# GPRS_A7.net
KiCad netlist of a schematic drawn in EAGLE
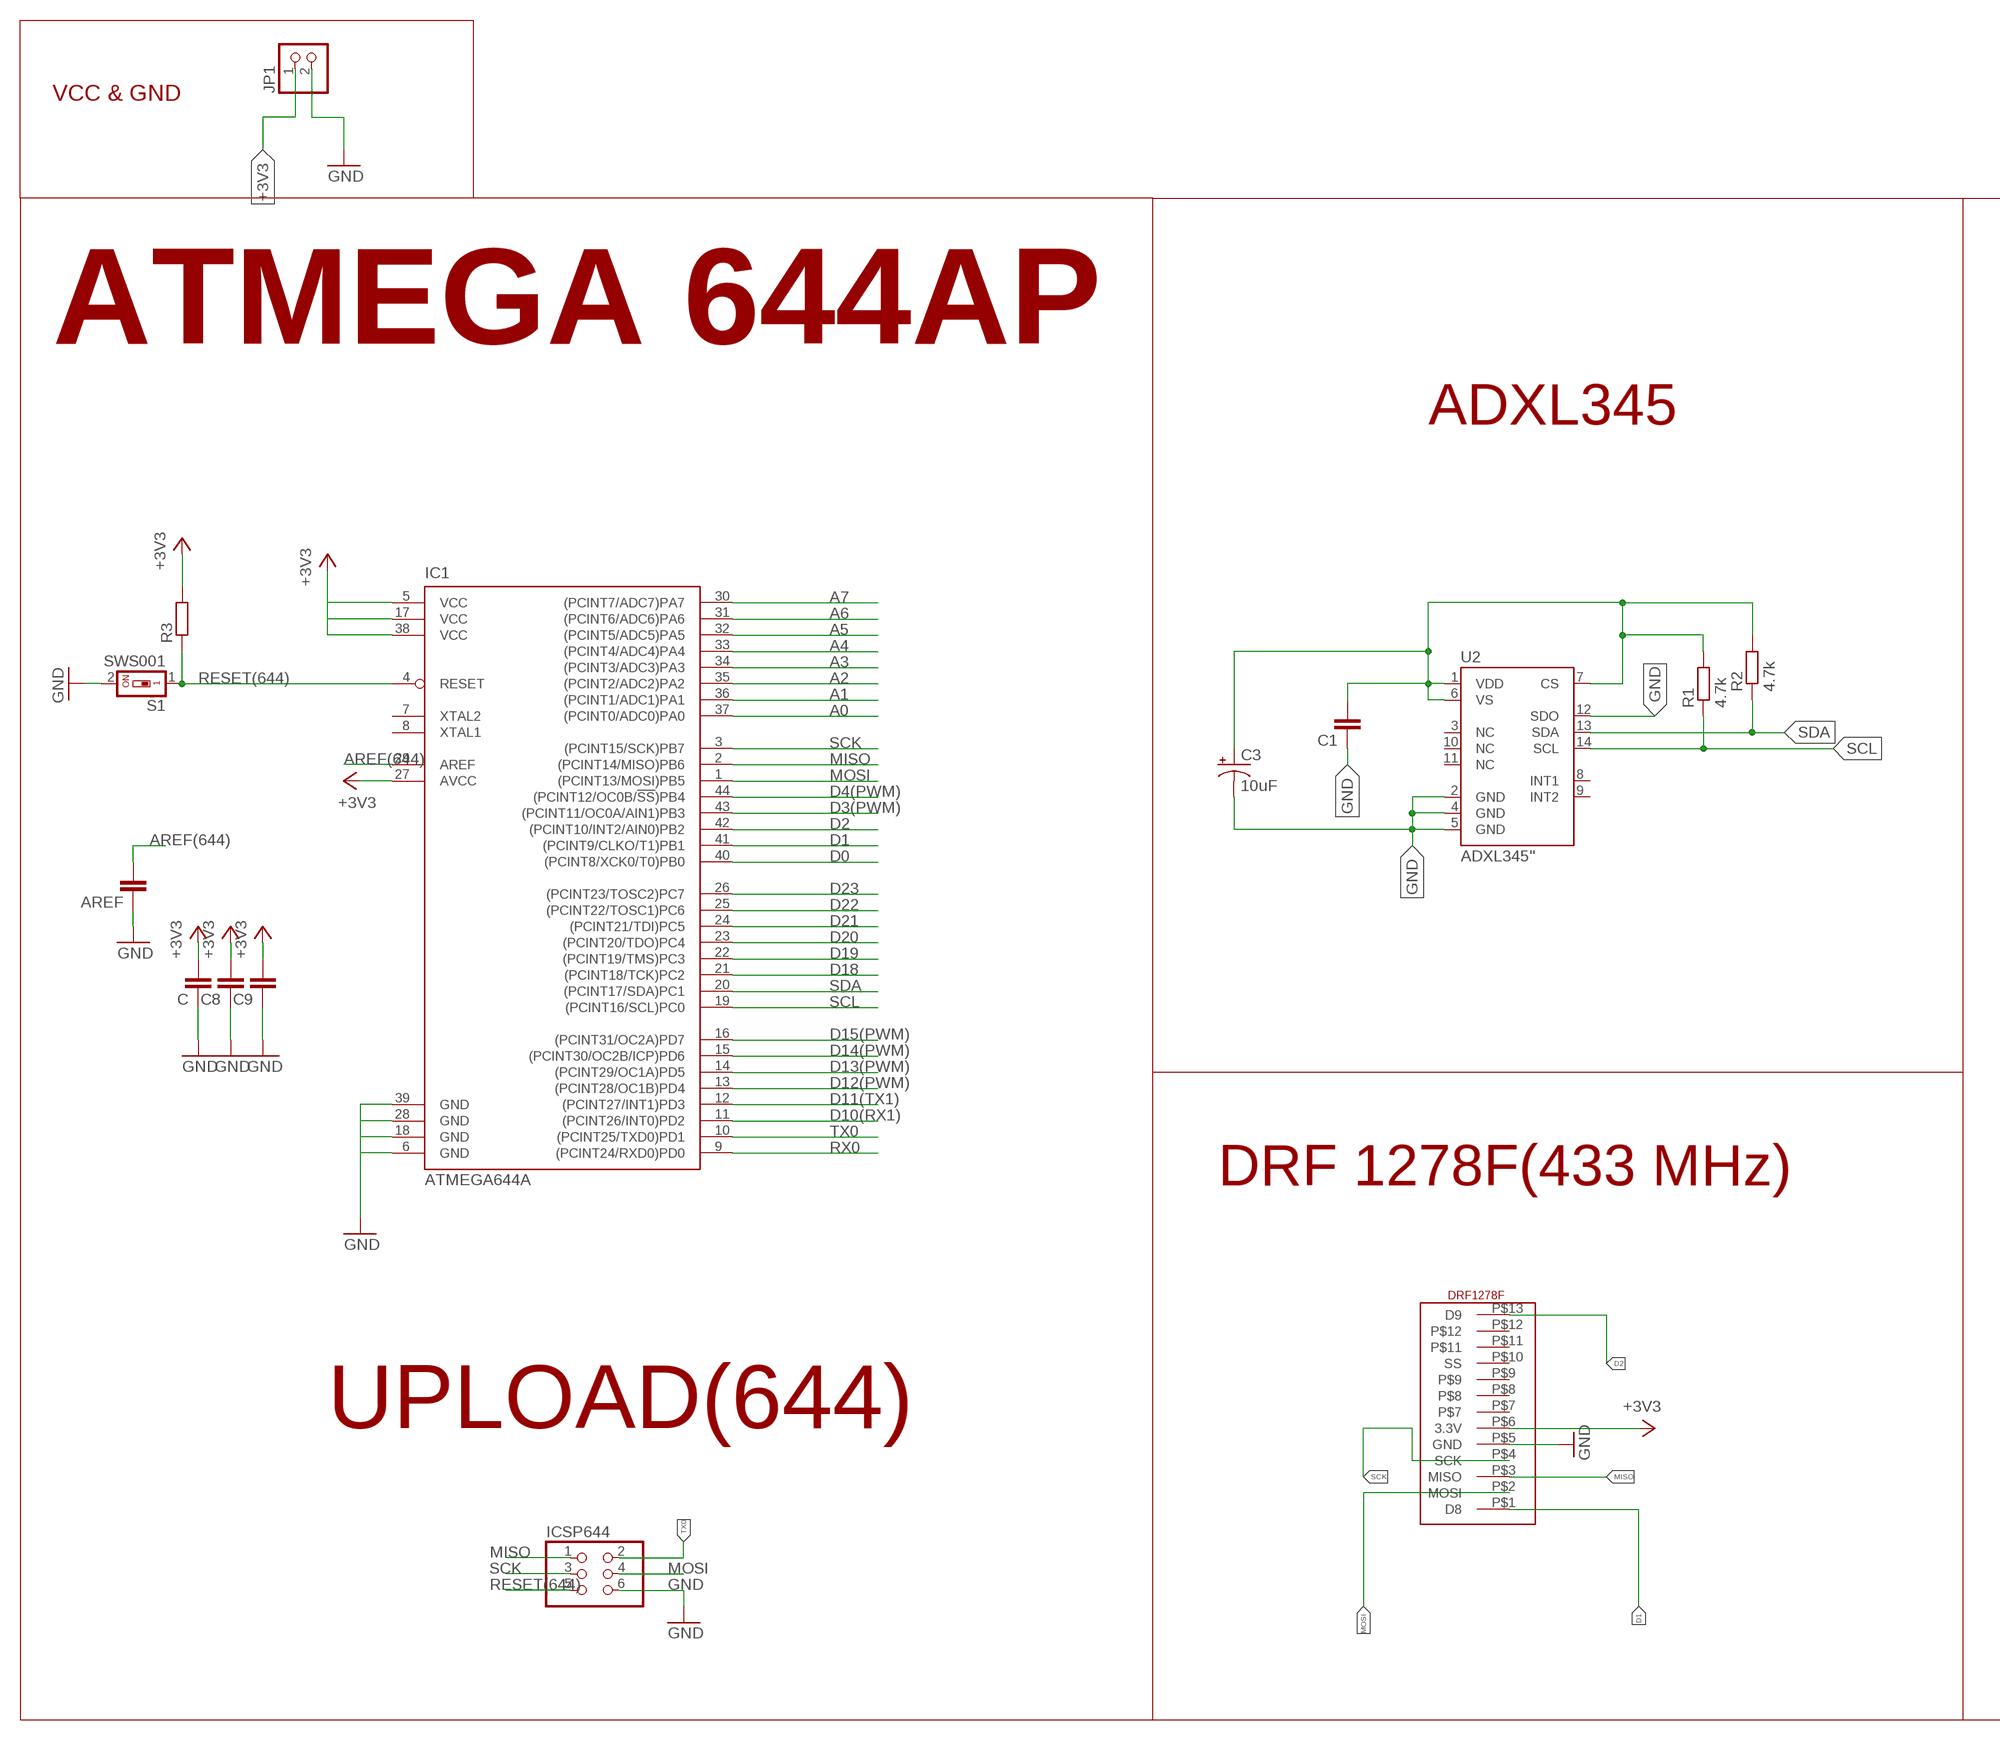
[diagram p0: schematic, sheet 1, part 1 of 2]
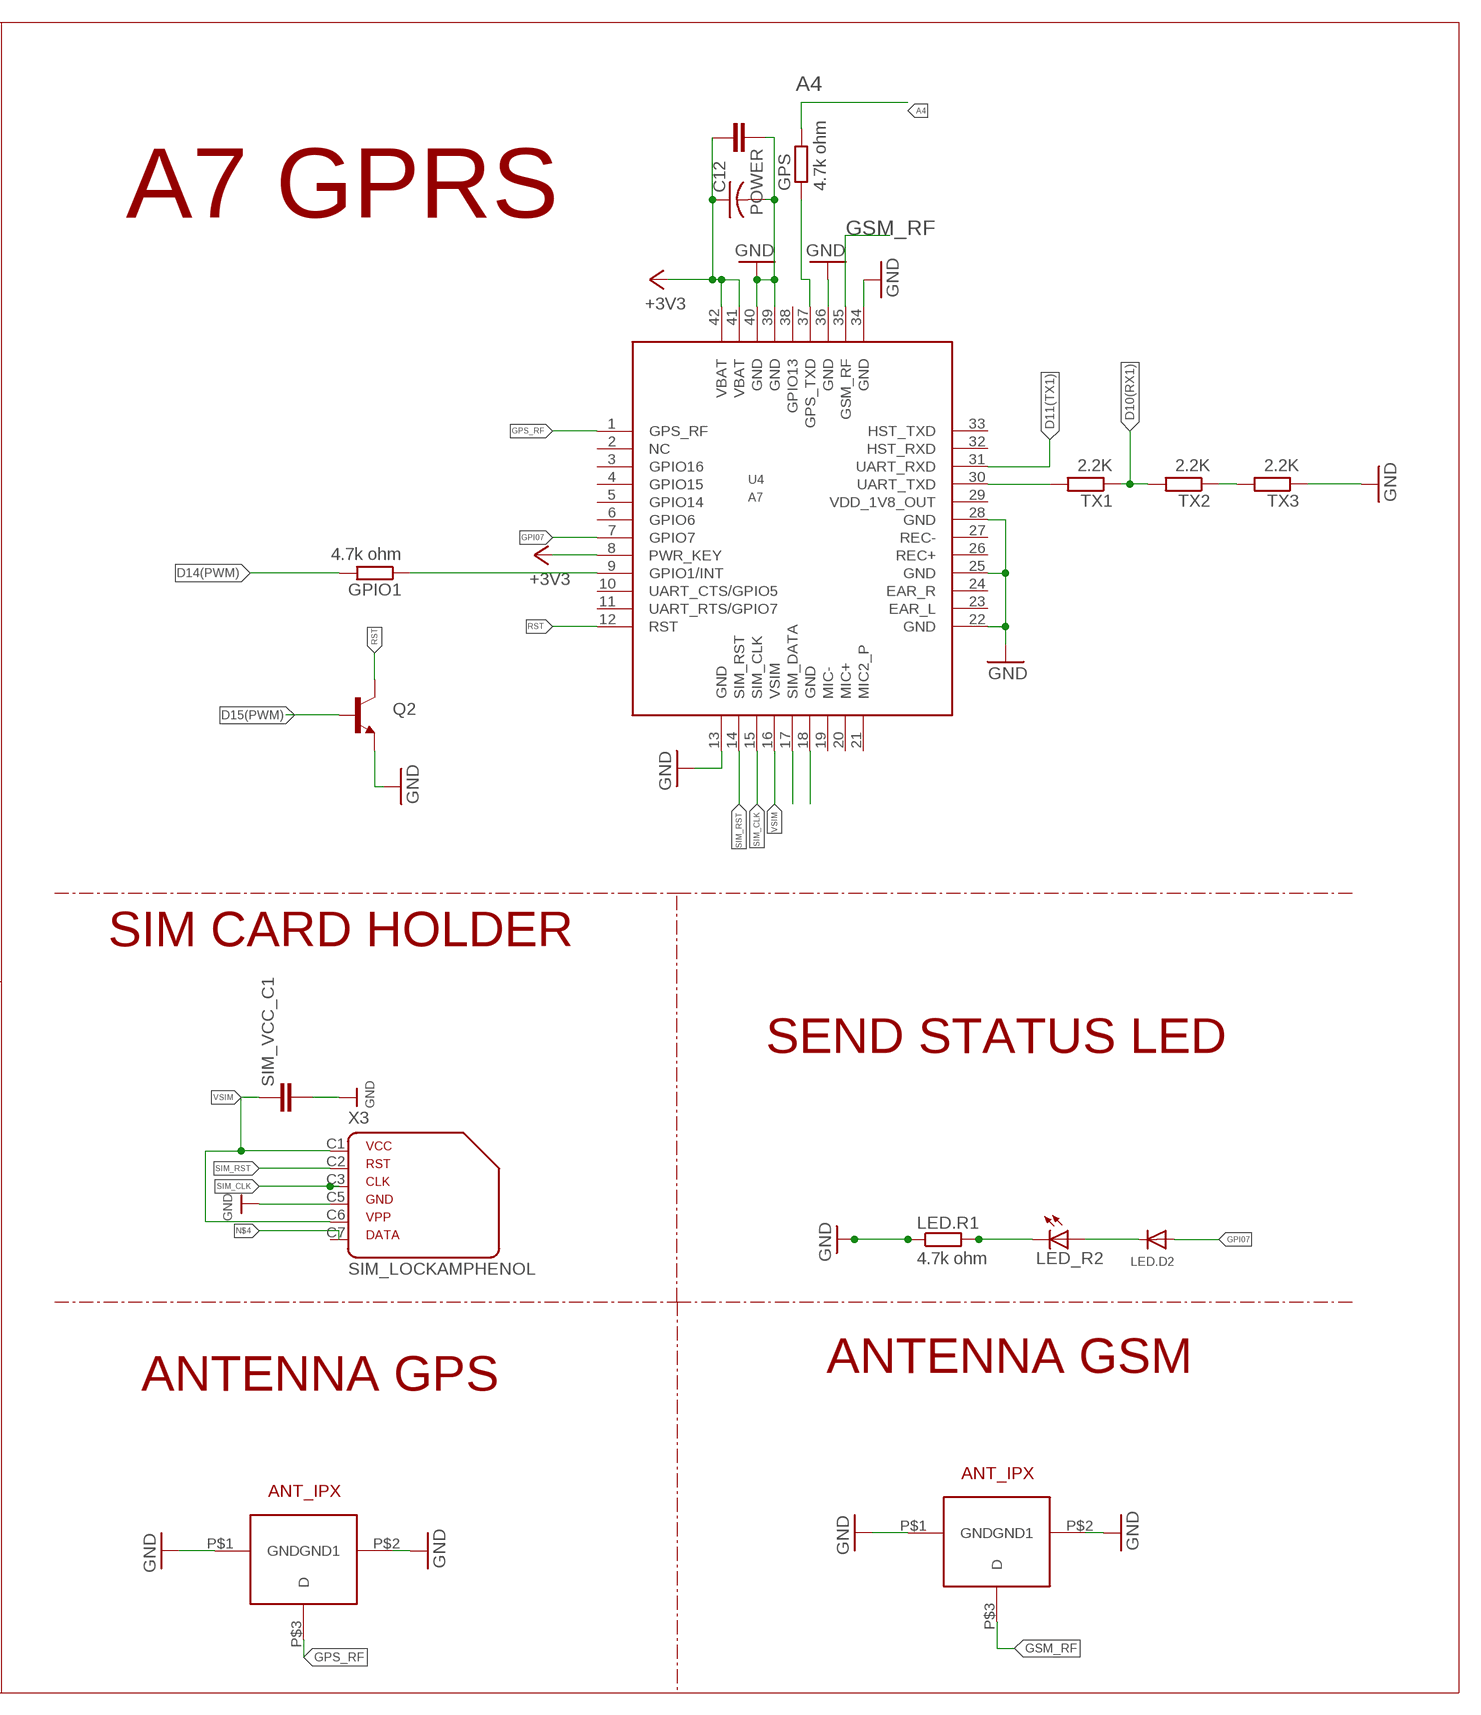
[diagram p1: schematic, sheet 1, part 2 of 2]

(export (version "E")
  (design (tool "Eeschema 10.0.6"))
  (components
    (comp (ref "AREF")
      (value "100nF")
      (footprint "eagle-import:C0805")
      (libsource (lib "eagle-import") (part "C-EUC0805"))
    )
    (comp (ref "C")
      (value "22 uF")
      (footprint "eagle-import:C0805")
      (libsource (lib "eagle-import") (part "C-EUC0805"))
    )
    (comp (ref "C1")
      (value "0.1uF")
      (footprint "eagle-import:C0805")
      (libsource (lib "eagle-import") (part "C-EUC0805"))
    )
    (comp (ref "C3")
      (value "10uF")
      (footprint "eagle-import:EIA3216")
      (libsource (lib "eagle-import") (part "CAP_POL1206"))
    )
    (comp (ref "C8")
      (value "100nF")
      (footprint "eagle-import:C0805")
      (libsource (lib "eagle-import") (part "C-EUC0805"))
    )
    (comp (ref "C9")
      (value "100nF")
      (footprint "eagle-import:C0805")
      (libsource (lib "eagle-import") (part "C-EUC0805"))
    )
    (comp (ref "C12")
      (value "C-US025-024X044")
      (footprint "eagle-import:C025-024X044")
      (libsource (lib "eagle-import") (part "C-US025-024X044"))
    )
    (comp (ref "GPIO1")
      (value "4.7k ohm")
      (footprint "eagle-import:R0805")
      (libsource (lib "eagle-import") (part "R-EU_R0805"))
    )
    (comp (ref "GPS")
      (value "4.7k ohm")
      (footprint "eagle-import:R0805")
      (libsource (lib "eagle-import") (part "R-EU_R0805"))
    )
    (comp (ref "IC1")
      (value "ATMEGA644A")
      (footprint "eagle-import:TQFP44")
      (fields (field (name "MPN") "ATMEGA644PV-10AU"))
      (libsource (lib "eagle-import") (part "ATMEGA644A"))
    )
    (comp (ref "ICSP644")
      (value "PINHD-2X3")
      (footprint "eagle-import:2X03")
      (libsource (lib "eagle-import") (part "PINHD-2X3"))
    )
    (comp (ref "JP1")
      (value "PINHD-1X2")
      (footprint "eagle-import:1X02")
      (libsource (lib "eagle-import") (part "PINHD-1X2"))
    )
    (comp (ref "LED.D2")
      (value "DIODESOD-123")
      (footprint "eagle-import:SOD-123")
      (libsource (lib "eagle-import") (part "DIODESOD-123"))
    )
    (comp (ref "LED.R1")
      (value "4.7k ohm")
      (footprint "eagle-import:R0805")
      (libsource (lib "eagle-import") (part "R-EU_R0805"))
    )
    (comp (ref "LED_R2")
      (value "LEDCHIP-LED0805")
      (footprint "eagle-import:CHIP-LED0805")
      (libsource (lib "eagle-import") (part "LEDCHIP-LED0805"))
    )
    (comp (ref "POWER")
      (value "100nF")
      (footprint "eagle-import:C0805")
      (libsource (lib "eagle-import") (part "C-EUC0805"))
    )
    (comp (ref "Q2")
      (value "TRANSISTOR_NPNSOT23-3")
      (footprint "eagle-import:SOT23-3")
      (libsource (lib "eagle-import") (part "TRANSISTOR_NPNSOT23-3"))
    )
    (comp (ref "R1")
      (value "4.7k")
      (footprint "eagle-import:R0805")
      (libsource (lib "eagle-import") (part "R-EU_R0805"))
    )
    (comp (ref "R2")
      (value "4.7k")
      (footprint "eagle-import:R0805")
      (libsource (lib "eagle-import") (part "R-EU_R0805"))
    )
    (comp (ref "R3")
      (value "R-EU_R0805")
      (footprint "eagle-import:R0805")
      (libsource (lib "eagle-import") (part "R-EU_R0805"))
    )
    (comp (ref "S1")
      (value "SWS001")
      (footprint "eagle-import:SMS-001")
      (libsource (lib "eagle-import") (part "SWS001"))
    )
    (comp (ref "SIM_VCC_C1")
      (value "100nF")
      (footprint "eagle-import:C0805")
      (libsource (lib "eagle-import") (part "C-EUC0805"))
    )
    (comp (ref "TX1")
      (value "2.2K")
      (footprint "eagle-import:R0805")
      (libsource (lib "eagle-import") (part "R-EU_R0805"))
    )
    (comp (ref "TX2")
      (value "2.2K")
      (footprint "eagle-import:R0805")
      (libsource (lib "eagle-import") (part "R-EU_R0805"))
    )
    (comp (ref "TX3")
      (value "2.2K")
      (footprint "eagle-import:R0805")
      (libsource (lib "eagle-import") (part "R-EU_R0805"))
    )
    (comp (ref "U$1")
      (value "DRF1278F")
      (footprint "eagle-import:DIP13")
      (libsource (lib "eagle-import") (part "DRF1278F"))
    )
    (comp (ref "U$2")
      (value "ANTENNA_IPX")
      (footprint "eagle-import:SMD3")
      (libsource (lib "eagle-import") (part "ANTENNA_IPX"))
    )
    (comp (ref "U$9")
      (value "ANTENNA_IPX")
      (footprint "eagle-import:SMD3")
      (libsource (lib "eagle-import") (part "ANTENNA_IPX"))
    )
    (comp (ref "U2")
      (value "ADXL345\"")
      (footprint "eagle-import:ADXL3451_1")
      (libsource (lib "eagle-import") (part "ADXL345{dblquote}"))
    )
    (comp (ref "U4") (value "A7") (footprint "eagle-import:A7") (libsource (lib "eagle-import") (part "A7")))
    (comp (ref "X3")
      (value "SIM_LOCKAMPHENOL")
      (footprint "eagle-import:C707_10M006_512_2")
      (libsource (lib "eagle-import") (part "SIM_LOCKAMPHENOL"))
    )
  )
  (nets
    (net (code "1") (name "+3V3") (class "Default")
      (node (ref "C") (pin "2") (pinfunction "2_2") (pintype "passive"))
      (node (ref "C12") (pin "1") (pinfunction "1_1") (pintype "passive"))
      (node (ref "C8") (pin "2") (pinfunction "2_2") (pintype "passive"))
      (node (ref "C9") (pin "2") (pinfunction "2_2") (pintype "passive"))
      (node (ref "IC1") (pin "17") (pinfunction "VCC_17") (pintype "power_in"))
      (node (ref "IC1") (pin "27") (pinfunction "AVCC_27") (pintype "power_in"))
      (node (ref "IC1") (pin "38") (pinfunction "VCC_38") (pintype "power_in"))
      (node (ref "IC1") (pin "5") (pinfunction "VCC_5") (pintype "power_in"))
      (node (ref "JP1") (pin "1") (pinfunction "1_1") (pintype "passive"))
      (node (ref "POWER") (pin "2") (pinfunction "2_2") (pintype "passive"))
      (node (ref "R3") (pin "2") (pinfunction "2_2") (pintype "passive"))
      (node (ref "U$1") (pin "P$6") (pinfunction "3.3V_P$6") (pintype "bidirectional"))
      (node (ref "U4") (pin "41") (pinfunction "VBAT_41") (pintype "bidirectional"))
      (node (ref "U4") (pin "42") (pinfunction "VBAT_42") (pintype "bidirectional"))
      (node (ref "U4") (pin "8") (pinfunction "PWR_KEY_8") (pintype "bidirectional"))
    )
    (net (code "2") (name "/A0") (class "Default")
      (node (ref "IC1") (pin "37") (pinfunction "(PCINT0/ADC0)PA0_37") (pintype "bidirectional"))
    )
    (net (code "3") (name "/A1") (class "Default")
      (node (ref "IC1") (pin "36") (pinfunction "(PCINT1/ADC1)PA1_36") (pintype "bidirectional"))
    )
    (net (code "4") (name "/A2") (class "Default")
      (node (ref "IC1") (pin "35") (pinfunction "(PCINT2/ADC2)PA2_35") (pintype "bidirectional"))
    )
    (net (code "5") (name "/A3") (class "Default")
      (node (ref "IC1") (pin "34") (pinfunction "(PCINT3/ADC3)PA3_34") (pintype "bidirectional"))
    )
    (net (code "6") (name "/A5") (class "Default")
      (node (ref "IC1") (pin "32") (pinfunction "(PCINT5/ADC5)PA5_32") (pintype "bidirectional"))
    )
    (net (code "7") (name "/A6") (class "Default")
      (node (ref "IC1") (pin "31") (pinfunction "(PCINT6/ADC6)PA6_31") (pintype "bidirectional"))
    )
    (net (code "8") (name "/A7") (class "Default")
      (node (ref "IC1") (pin "30") (pinfunction "(PCINT7/ADC7)PA7_30") (pintype "bidirectional"))
    )
    (net (code "9") (name "/AREF(644)") (class "Default")
      (node (ref "AREF") (pin "2") (pinfunction "2_2") (pintype "passive"))
      (node (ref "IC1") (pin "29") (pinfunction "AREF_29") (pintype "passive"))
    )
    (net (code "10") (name "/D0") (class "Default")
      (node (ref "IC1") (pin "40") (pinfunction "(PCINT8/XCK0/T0)PB0_40") (pintype "bidirectional"))
    )
    (net (code "11") (name "/D3(PWM)") (class "Default")
      (node (ref "IC1") (pin "43") (pinfunction "(PCINT11/OC0A/AIN1)PB3_43") (pintype "bidirectional"))
    )
    (net (code "12") (name "/D4(PWM)") (class "Default")
      (node (ref "IC1") (pin "44") (pinfunction "(PCINT12/OC0B/~{SS})PB4_44") (pintype "bidirectional"))
    )
    (net (code "13") (name "/D12(PWM)") (class "Default")
      (node (ref "IC1") (pin "13") (pinfunction "(PCINT28/OC1B)PD4_13") (pintype "bidirectional"))
    )
    (net (code "14") (name "/D13(PWM)") (class "Default")
      (node (ref "IC1") (pin "14") (pinfunction "(PCINT29/OC1A)PD5_14") (pintype "bidirectional"))
    )
    (net (code "15") (name "/D18") (class "Default")
      (node (ref "IC1") (pin "21") (pinfunction "(PCINT18/TCK)PC2_21") (pintype "output"))
    )
    (net (code "16") (name "/D19") (class "Default")
      (node (ref "IC1") (pin "22") (pinfunction "(PCINT19/TMS)PC3_22") (pintype "output"))
    )
    (net (code "17") (name "/D20") (class "Default")
      (node (ref "IC1") (pin "23") (pinfunction "(PCINT20/TDO)PC4_23") (pintype "output"))
    )
    (net (code "18") (name "/D21") (class "Default")
      (node (ref "IC1") (pin "24") (pinfunction "(PCINT21/TDI)PC5_24") (pintype "output"))
    )
    (net (code "19") (name "/D22") (class "Default")
      (node (ref "IC1") (pin "25") (pinfunction "(PCINT22/TOSC1)PC6_25") (pintype "output"))
    )
    (net (code "20") (name "/D23") (class "Default")
      (node (ref "IC1") (pin "26") (pinfunction "(PCINT23/TOSC2)PC7_26") (pintype "output"))
    )
    (net (code "21") (name "/RESET(644)") (class "Default")
      (node (ref "IC1") (pin "4") (pinfunction "RESET_4") (pintype "input"))
      (node (ref "ICSP644") (pin "5") (pinfunction "5_5") (pintype "passive"))
      (node (ref "R3") (pin "1") (pinfunction "1_1") (pintype "passive"))
      (node (ref "S1") (pin "1") (pinfunction "1_1") (pintype "passive"))
    )
    (net (code "22") (name "/RX0") (class "Default")
      (node (ref "IC1") (pin "9") (pinfunction "(PCINT24/RXD0)PD0_9") (pintype "bidirectional"))
    )
    (net (code "23") (name "A4") (class "Default")
      (node (ref "GPS") (pin "2") (pinfunction "2_2") (pintype "passive"))
      (node (ref "IC1") (pin "33") (pinfunction "(PCINT4/ADC4)PA4_33") (pintype "bidirectional"))
    )
    (net (code "24") (name "D1") (class "Default")
      (node (ref "IC1") (pin "41") (pinfunction "(PCINT9/CLKO/T1)PB1_41") (pintype "bidirectional"))
      (node (ref "U$1") (pin "P$1") (pinfunction "D8_P$1") (pintype "bidirectional"))
    )
    (net (code "25") (name "D2") (class "Default")
      (node (ref "IC1") (pin "42") (pinfunction "(PCINT10/INT2/AIN0)PB2_42") (pintype "bidirectional"))
      (node (ref "U$1") (pin "P$13") (pinfunction "D9_P$13") (pintype "bidirectional"))
    )
    (net (code "26") (name "D10(RX1)") (class "Default")
      (node (ref "IC1") (pin "11") (pinfunction "(PCINT26/INT0)PD2_11") (pintype "bidirectional"))
      (node (ref "TX1") (pin "1") (pinfunction "1_1") (pintype "passive"))
      (node (ref "TX2") (pin "2") (pinfunction "2_2") (pintype "passive"))
    )
    (net (code "27") (name "D11(TX1)") (class "Default")
      (node (ref "IC1") (pin "12") (pinfunction "(PCINT27/INT1)PD3_12") (pintype "bidirectional"))
      (node (ref "U4") (pin "31") (pinfunction "UART_RXD_31") (pintype "bidirectional"))
    )
    (net (code "28") (name "D14(PWM)") (class "Default")
      (node (ref "GPIO1") (pin "2") (pinfunction "2_2") (pintype "passive"))
      (node (ref "IC1") (pin "15") (pinfunction "(PCINT30/OC2B/ICP)PD6_15") (pintype "bidirectional"))
    )
    (net (code "29") (name "D15(PWM)") (class "Default")
      (node (ref "IC1") (pin "16") (pinfunction "(PCINT31/OC2A)PD7_16") (pintype "bidirectional"))
      (node (ref "Q2") (pin "1") (pinfunction "B_1") (pintype "passive"))
    )
    (net (code "30") (name "GND") (class "Default")
      (node (ref "AREF") (pin "1") (pinfunction "1_1") (pintype "passive"))
      (node (ref "C") (pin "1") (pinfunction "1_1") (pintype "passive"))
      (node (ref "C1") (pin "1") (pinfunction "1_1") (pintype "passive"))
      (node (ref "C12") (pin "2") (pinfunction "2_2") (pintype "passive"))
      (node (ref "C3") (pin "C") (pinfunction "-_C") (pintype "passive"))
      (node (ref "C8") (pin "1") (pinfunction "1_1") (pintype "passive"))
      (node (ref "C9") (pin "1") (pinfunction "1_1") (pintype "passive"))
      (node (ref "IC1") (pin "18") (pinfunction "GND_18") (pintype "power_in"))
      (node (ref "IC1") (pin "28") (pinfunction "GND_28") (pintype "power_in"))
      (node (ref "IC1") (pin "39") (pinfunction "GND_39") (pintype "power_in"))
      (node (ref "IC1") (pin "6") (pinfunction "GND_6") (pintype "power_in"))
      (node (ref "ICSP644") (pin "6") (pinfunction "6_6") (pintype "passive"))
      (node (ref "JP1") (pin "2") (pinfunction "2_2") (pintype "passive"))
      (node (ref "LED.R1") (pin "1") (pinfunction "1_1") (pintype "passive"))
      (node (ref "POWER") (pin "1") (pinfunction "1_1") (pintype "passive"))
      (node (ref "Q2") (pin "2") (pinfunction "E_2") (pintype "passive"))
      (node (ref "S1") (pin "2") (pinfunction "2_2") (pintype "passive"))
      (node (ref "SIM_VCC_C1") (pin "2") (pinfunction "2_2") (pintype "passive"))
      (node (ref "TX3") (pin "1") (pinfunction "1_1") (pintype "passive"))
      (node (ref "U$1") (pin "P$5") (pinfunction "GND_P$5") (pintype "bidirectional"))
      (node (ref "U$2") (pin "P$1") (pinfunction "GND_P$1") (pintype "bidirectional"))
      (node (ref "U$2") (pin "P$2") (pinfunction "GND1_P$2") (pintype "bidirectional"))
      (node (ref "U$9") (pin "P$1") (pinfunction "GND_P$1") (pintype "bidirectional"))
      (node (ref "U$9") (pin "P$2") (pinfunction "GND1_P$2") (pintype "bidirectional"))
      (node (ref "U2") (pin "12") (pinfunction "SDO_12") (pintype "bidirectional"))
      (node (ref "U2") (pin "2") (pinfunction "GND_2") (pintype "bidirectional"))
      (node (ref "U2") (pin "4") (pinfunction "GND_4") (pintype "bidirectional"))
      (node (ref "U2") (pin "5") (pinfunction "GND_5") (pintype "bidirectional"))
      (node (ref "U4") (pin "13") (pinfunction "GND_13") (pintype "bidirectional"))
      (node (ref "U4") (pin "22") (pinfunction "GND_22") (pintype "bidirectional"))
      (node (ref "U4") (pin "25") (pinfunction "GND_25") (pintype "bidirectional"))
      (node (ref "U4") (pin "28") (pinfunction "GND_28") (pintype "bidirectional"))
      (node (ref "U4") (pin "34") (pinfunction "GND_34") (pintype "bidirectional"))
      (node (ref "U4") (pin "36") (pinfunction "GND_36") (pintype "bidirectional"))
      (node (ref "U4") (pin "39") (pinfunction "GND_39") (pintype "bidirectional"))
      (node (ref "U4") (pin "40") (pinfunction "GND_40") (pintype "bidirectional"))
      (node (ref "X3") (pin "C5") (pinfunction "4_C5") (pintype "passive"))
    )
    (net (code "31") (name "GPI07") (class "Default")
      (node (ref "LED.D2") (pin "A") (pinfunction "A_A") (pintype "passive"))
      (node (ref "U4") (pin "7") (pinfunction "GPIO7_7") (pintype "bidirectional"))
    )
    (net (code "32") (name "GPS_RF") (class "Default")
      (node (ref "U$2") (pin "P$3") (pinfunction "D_P$3") (pintype "bidirectional"))
      (node (ref "U4") (pin "1") (pinfunction "GPS_RF_1") (pintype "bidirectional"))
    )
    (net (code "33") (name "GSM_RF") (class "Default")
      (node (ref "U$9") (pin "P$3") (pinfunction "D_P$3") (pintype "bidirectional"))
      (node (ref "U4") (pin "35") (pinfunction "GSM_RF_35") (pintype "bidirectional"))
    )
    (net (code "34") (name "MISO") (class "Default")
      (node (ref "IC1") (pin "2") (pinfunction "(PCINT14/MISO)PB6_2") (pintype "bidirectional"))
      (node (ref "ICSP644") (pin "1") (pinfunction "1_1") (pintype "passive"))
      (node (ref "U$1") (pin "P$3") (pinfunction "MISO_P$3") (pintype "bidirectional"))
    )
    (net (code "35") (name "MOSI") (class "Default")
      (node (ref "IC1") (pin "1") (pinfunction "(PCINT13/MOSI)PB5_1") (pintype "bidirectional"))
      (node (ref "ICSP644") (pin "4") (pinfunction "4_4") (pintype "passive"))
      (node (ref "U$1") (pin "P$2") (pinfunction "MOSI_P$2") (pintype "bidirectional"))
    )
    (net (code "37") (name "Net-(C3-+)") (class "Default")
      (node (ref "C1") (pin "2") (pinfunction "2_2") (pintype "passive"))
      (node (ref "C3") (pin "A") (pinfunction "+_A") (pintype "passive"))
      (node (ref "R1") (pin "2") (pinfunction "2_2") (pintype "passive"))
      (node (ref "R2") (pin "2") (pinfunction "2_2") (pintype "passive"))
      (node (ref "U2") (pin "1") (pinfunction "VDD_1") (pintype "bidirectional"))
      (node (ref "U2") (pin "6") (pinfunction "VS_6") (pintype "bidirectional"))
      (node (ref "U2") (pin "7") (pinfunction "CS_7") (pintype "bidirectional"))
    )
    (net (code "38") (name "Net-(LED.D2-PadC)") (class "Default")
      (node (ref "LED.D2") (pin "C") (pinfunction "C_C") (pintype "passive"))
      (node (ref "LED_R2") (pin "A") (pinfunction "A_A") (pintype "passive"))
    )
    (net (code "39") (name "Net-(LED.R1-Pad2)") (class "Default")
      (node (ref "LED.R1") (pin "2") (pinfunction "2_2") (pintype "passive"))
      (node (ref "LED_R2") (pin "C") (pinfunction "C_C") (pintype "passive"))
    )
    (net (code "40") (name "Net-(TX2-Pad1)") (class "Default")
      (node (ref "TX2") (pin "1") (pinfunction "1_1") (pintype "passive"))
      (node (ref "TX3") (pin "2") (pinfunction "2_2") (pintype "passive"))
    )
    (net (code "41") (name "Net-(U4-GPIO1{slash}INT)") (class "Default")
      (node (ref "GPIO1") (pin "1") (pinfunction "1_1") (pintype "passive"))
      (node (ref "U4") (pin "9") (pinfunction "GPIO1/INT_9") (pintype "bidirectional"))
    )
    (net (code "42") (name "Net-(U4-GPS_TXD)") (class "Default")
      (node (ref "GPS") (pin "1") (pinfunction "1_1") (pintype "passive"))
      (node (ref "U4") (pin "37") (pinfunction "GPS_TXD_37") (pintype "bidirectional"))
    )
    (net (code "43") (name "Net-(U4-UART_TXD)") (class "Default")
      (node (ref "TX1") (pin "2") (pinfunction "2_2") (pintype "passive"))
      (node (ref "U4") (pin "30") (pinfunction "UART_TXD_30") (pintype "bidirectional"))
    )
    (net (code "44") (name "RST") (class "Default")
      (node (ref "Q2") (pin "3") (pinfunction "C_3") (pintype "passive"))
      (node (ref "U4") (pin "12") (pinfunction "RST_12") (pintype "bidirectional"))
    )
    (net (code "45") (name "SCK") (class "Default")
      (node (ref "IC1") (pin "3") (pinfunction "(PCINT15/SCK)PB7_3") (pintype "bidirectional"))
      (node (ref "ICSP644") (pin "3") (pinfunction "3_3") (pintype "passive"))
      (node (ref "U$1") (pin "P$4") (pinfunction "SCK_P$4") (pintype "bidirectional"))
    )
    (net (code "46") (name "SCL") (class "Default")
      (node (ref "IC1") (pin "19") (pinfunction "(PCINT16/SCL)PC0_19") (pintype "output"))
      (node (ref "R1") (pin "1") (pinfunction "1_1") (pintype "passive"))
      (node (ref "U2") (pin "14") (pinfunction "SCL_14") (pintype "bidirectional"))
    )
    (net (code "47") (name "SDA") (class "Default")
      (node (ref "IC1") (pin "20") (pinfunction "(PCINT17/SDA)PC1_20") (pintype "output"))
      (node (ref "R2") (pin "1") (pinfunction "1_1") (pintype "passive"))
      (node (ref "U2") (pin "13") (pinfunction "SDA_13") (pintype "bidirectional"))
    )
    (net (code "48") (name "SIM_CLK") (class "Default")
      (node (ref "U4") (pin "15") (pinfunction "SIM_CLK_15") (pintype "bidirectional"))
      (node (ref "X3") (pin "C3") (pinfunction "3_C3") (pintype "passive"))
    )
    (net (code "49") (name "SIM_RST") (class "Default")
      (node (ref "U4") (pin "14") (pinfunction "SIM_RST_14") (pintype "bidirectional"))
      (node (ref "X3") (pin "C2") (pinfunction "2_C2") (pintype "passive"))
    )
    (net (code "50") (name "TX0") (class "Default")
      (node (ref "IC1") (pin "10") (pinfunction "(PCINT25/TXD0)PD1_10") (pintype "bidirectional"))
      (node (ref "ICSP644") (pin "2") (pinfunction "2_2") (pintype "passive"))
    )
    (net (code "51") (name "VSIM") (class "Default")
      (node (ref "SIM_VCC_C1") (pin "1") (pinfunction "1_1") (pintype "passive"))
      (node (ref "U4") (pin "16") (pinfunction "VSIM_16") (pintype "bidirectional"))
      (node (ref "X3") (pin "C1") (pinfunction "1_C1") (pintype "passive"))
      (node (ref "X3") (pin "C6") (pinfunction "5_C6") (pintype "passive"))
    )
    (net (code "52") (name "unconnected-(IC1-XTAL1-Pad8)") (class "Default")
      (node (ref "IC1") (pin "8") (pinfunction "XTAL1_8") (pintype "bidirectional"))
    )
    (net (code "53") (name "unconnected-(IC1-XTAL2-Pad7)") (class "Default")
      (node (ref "IC1") (pin "7") (pinfunction "XTAL2_7") (pintype "bidirectional"))
    )
    (net (code "54") (name "unconnected-(U$1-PadP$7)") (class "Default")
      (node (ref "U$1") (pin "P$7") (pinfunction "P$7_P$7") (pintype "bidirectional"))
    )
    (net (code "55") (name "unconnected-(U$1-PadP$8)") (class "Default")
      (node (ref "U$1") (pin "P$8") (pinfunction "P$8_P$8") (pintype "bidirectional"))
    )
    (net (code "56") (name "unconnected-(U$1-PadP$9)") (class "Default")
      (node (ref "U$1") (pin "P$9") (pinfunction "P$9_P$9") (pintype "bidirectional"))
    )
    (net (code "57") (name "unconnected-(U$1-PadP$11)") (class "Default")
      (node (ref "U$1") (pin "P$11") (pinfunction "P$11_P$11") (pintype "bidirectional"))
    )
    (net (code "58") (name "unconnected-(U$1-PadP$12)") (class "Default")
      (node (ref "U$1") (pin "P$12") (pinfunction "P$12_P$12") (pintype "bidirectional"))
    )
    (net (code "59") (name "unconnected-(U$1-SS-PadP$10)") (class "Default")
      (node (ref "U$1") (pin "P$10") (pinfunction "SS_P$10") (pintype "bidirectional"))
    )
    (net (code "60") (name "unconnected-(U2-INT1-Pad8)") (class "Default")
      (node (ref "U2") (pin "8") (pinfunction "INT1_8") (pintype "bidirectional"))
    )
    (net (code "61") (name "unconnected-(U2-INT2-Pad9)") (class "Default")
      (node (ref "U2") (pin "9") (pinfunction "INT2_9") (pintype "bidirectional"))
    )
    (net (code "62") (name "unconnected-(U2-NC-Pad3)") (class "Default")
      (node (ref "U2") (pin "3") (pinfunction "NC_3") (pintype "bidirectional"))
    )
    (net (code "63") (name "unconnected-(U2-NC-Pad10)") (class "Default")
      (node (ref "U2") (pin "10") (pinfunction "NC_10") (pintype "bidirectional"))
    )
    (net (code "64") (name "unconnected-(U2-NC-Pad11)") (class "Default")
      (node (ref "U2") (pin "11") (pinfunction "NC_11") (pintype "bidirectional"))
    )
    (net (code "65") (name "unconnected-(U4-EAR_L-Pad23)") (class "Default")
      (node (ref "U4") (pin "23") (pinfunction "EAR_L_23") (pintype "bidirectional"))
    )
    (net (code "66") (name "unconnected-(U4-EAR_R-Pad24)") (class "Default")
      (node (ref "U4") (pin "24") (pinfunction "EAR_R_24") (pintype "bidirectional"))
    )
    (net (code "67") (name "unconnected-(U4-GND-Pad18)") (class "Default")
      (node (ref "U4") (pin "18") (pinfunction "GND_18") (pintype "bidirectional"))
    )
    (net (code "68") (name "unconnected-(U4-GPIO6-Pad6)") (class "Default")
      (node (ref "U4") (pin "6") (pinfunction "GPIO6_6") (pintype "bidirectional"))
    )
    (net (code "69") (name "unconnected-(U4-GPIO13-Pad38)") (class "Default")
      (node (ref "U4") (pin "38") (pinfunction "GPIO13_38") (pintype "bidirectional"))
    )
    (net (code "70") (name "unconnected-(U4-GPIO14-Pad5)") (class "Default")
      (node (ref "U4") (pin "5") (pinfunction "GPIO14_5") (pintype "bidirectional"))
    )
    (net (code "71") (name "unconnected-(U4-GPIO15-Pad4)") (class "Default")
      (node (ref "U4") (pin "4") (pinfunction "GPIO15_4") (pintype "bidirectional"))
    )
    (net (code "72") (name "unconnected-(U4-GPIO16-Pad3)") (class "Default")
      (node (ref "U4") (pin "3") (pinfunction "GPIO16_3") (pintype "bidirectional"))
    )
    (net (code "73") (name "unconnected-(U4-HST_RXD-Pad32)") (class "Default")
      (node (ref "U4") (pin "32") (pinfunction "HST_RXD_32") (pintype "bidirectional"))
    )
    (net (code "74") (name "unconnected-(U4-HST_TXD-Pad33)") (class "Default")
      (node (ref "U4") (pin "33") (pinfunction "HST_TXD_33") (pintype "bidirectional"))
    )
    (net (code "75") (name "unconnected-(U4-MIC+-Pad20)") (class "Default")
      (node (ref "U4") (pin "20") (pinfunction "MIC+_20") (pintype "bidirectional"))
    )
    (net (code "76") (name "unconnected-(U4-MIC--Pad19)") (class "Default")
      (node (ref "U4") (pin "19") (pinfunction "MIC-_19") (pintype "bidirectional"))
    )
    (net (code "77") (name "unconnected-(U4-MIC2_P-Pad21)") (class "Default")
      (node (ref "U4") (pin "21") (pinfunction "MIC2_P_21") (pintype "bidirectional"))
    )
    (net (code "78") (name "unconnected-(U4-NC-Pad2)") (class "Default")
      (node (ref "U4") (pin "2") (pinfunction "NC_2") (pintype "bidirectional"))
    )
    (net (code "79") (name "unconnected-(U4-REC+-Pad26)") (class "Default")
      (node (ref "U4") (pin "26") (pinfunction "REC+_26") (pintype "bidirectional"))
    )
    (net (code "80") (name "unconnected-(U4-REC--Pad27)") (class "Default")
      (node (ref "U4") (pin "27") (pinfunction "REC-_27") (pintype "bidirectional"))
    )
    (net (code "81") (name "unconnected-(U4-SIM_DATA-Pad17)") (class "Default")
      (node (ref "U4") (pin "17") (pinfunction "SIM_DATA_17") (pintype "bidirectional"))
    )
    (net (code "82") (name "unconnected-(U4-UART_CTS{slash}GPIO5-Pad10)") (class "Default")
      (node (ref "U4") (pin "10") (pinfunction "UART_CTS/GPIO5_10") (pintype "bidirectional"))
    )
    (net (code "83") (name "unconnected-(U4-UART_RTS{slash}GPIO7-Pad11)") (class "Default")
      (node (ref "U4") (pin "11") (pinfunction "UART_RTS/GPIO7_11") (pintype "bidirectional"))
    )
    (net (code "84") (name "unconnected-(U4-VDD_1V8_OUT-Pad29)") (class "Default")
      (node (ref "U4") (pin "29") (pinfunction "VDD_1V8_OUT_29") (pintype "bidirectional"))
    )
    (net (code "85") (name "unconnected-(X3-6-PadC7)") (class "Default")
      (node (ref "X3") (pin "C7") (pinfunction "6_C7") (pintype "passive"))
    )
  )
)
